# I2C_Breakout.net
KiCad netlist of a schematic drawn in Altium Designer
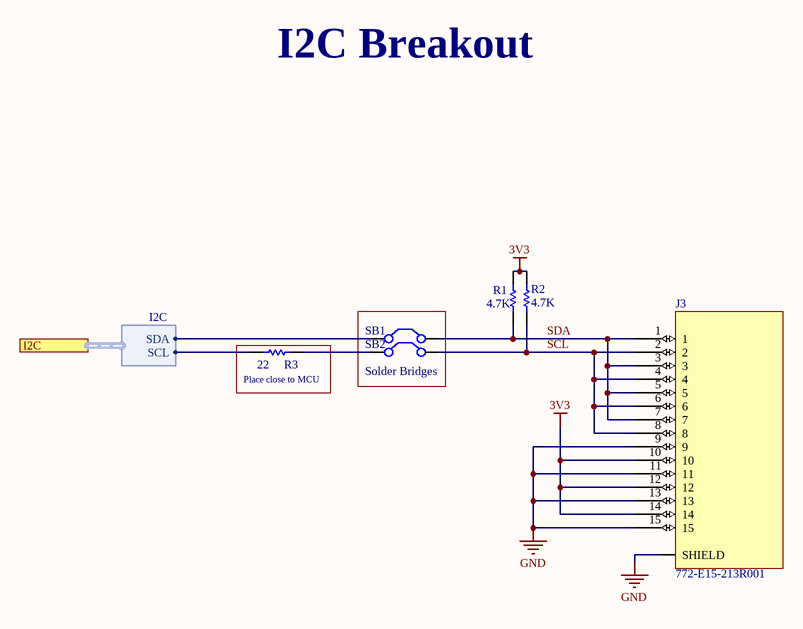
[diagram p0: I2C_Breakout.SchDoc]

(export (version "E")
  (design (tool "Eeschema 10.0.6"))
  (components
    (comp (ref "J3")
      (value "772-E15-213R001")
      (footprint "LaunchyRIOFootprints:15-Pos D-Sub")
      (description "15-Position Connector")
      (fields (field (name "DIGIKEY PART NUMBER") "NOR1010-ND"))
      (libsource (lib "LaunchyRIOComponents") (part "15-Position Connector"))
    )
    (comp (ref "R1")
      (value "4.7K")
      (footprint "0402")
      (description "Resistor")
      (fields (field (name "Comment") "Res1"))
      (libsource (lib "Miscellaneous Devices") (part "Res1"))
    )
    (comp (ref "R2")
      (value "4.7K")
      (footprint "0402")
      (description "Resistor")
      (fields (field (name "Comment") "Res1"))
      (libsource (lib "Miscellaneous Devices") (part "Res1"))
    )
    (comp (ref "R3")
      (value "22")
      (footprint "0402")
      (description "Resistor")
      (fields (field (name "Comment") "Res1"))
      (libsource (lib "Miscellaneous Devices") (part "Res1"))
    )
    (comp (ref "SB1")
      (value "Solder Bridge")
      (footprint "SB-2pos")
      (description "Jumper Wire")
      (libsource (lib "Miscellaneous Devices") (part "Jumper"))
    )
    (comp (ref "SB2")
      (value "Solder Bridge")
      (footprint "SB-2pos")
      (description "Jumper Wire")
      (libsource (lib "Miscellaneous Devices") (part "Jumper"))
    )
  )
  (nets
    (net (code "2") (name "/SCL") (class "Default")
      (node (ref "J3") (pin "2") (pinfunction "2_2") (pintype "bidirectional"))
      (node (ref "J3") (pin "4") (pinfunction "4_4") (pintype "bidirectional"))
      (node (ref "J3") (pin "6") (pinfunction "6_6") (pintype "bidirectional"))
      (node (ref "J3") (pin "8") (pinfunction "8_8") (pintype "bidirectional"))
      (node (ref "R2") (pin "1") (pinfunction "1_1") (pintype "passive"))
      (node (ref "SB2") (pin "2") (pinfunction "C2_2") (pintype "passive"))
    )
    (net (code "3") (name "/SDA") (class "Default")
      (node (ref "J3") (pin "1") (pinfunction "1_1") (pintype "bidirectional"))
      (node (ref "J3") (pin "3") (pinfunction "3_3") (pintype "bidirectional"))
      (node (ref "J3") (pin "5") (pinfunction "5_5") (pintype "bidirectional"))
      (node (ref "J3") (pin "7") (pinfunction "7_7") (pintype "bidirectional"))
      (node (ref "R1") (pin "1") (pinfunction "1_1") (pintype "passive"))
      (node (ref "SB1") (pin "2") (pinfunction "C2_2") (pintype "passive"))
    )
    (net (code "5") (name "3V3") (class "Default")
      (node (ref "J3") (pin "10") (pinfunction "10_10") (pintype "bidirectional"))
      (node (ref "J3") (pin "12") (pinfunction "12_12") (pintype "bidirectional"))
      (node (ref "J3") (pin "14") (pinfunction "14_14") (pintype "bidirectional"))
      (node (ref "R1") (pin "2") (pinfunction "2_2") (pintype "passive"))
      (node (ref "R2") (pin "2") (pinfunction "2_2") (pintype "passive"))
    )
    (net (code "6") (name "GND") (class "Default")
      (node (ref "J3") (pin "11") (pinfunction "11_11") (pintype "bidirectional"))
      (node (ref "J3") (pin "13") (pinfunction "13_13") (pintype "bidirectional"))
      (node (ref "J3") (pin "15") (pinfunction "15_15") (pintype "bidirectional"))
      (node (ref "J3") (pin "9") (pinfunction "9_9") (pintype "bidirectional"))
      (node (ref "J3") (pin "SHIELD") (pinfunction "SHIELD_SHIELD") (pintype "passive"))
    )
    (net (code "7") (name "Net-(SB2-C1)") (class "Default")
      (node (ref "R3") (pin "2") (pinfunction "2_2") (pintype "passive"))
      (node (ref "SB2") (pin "1") (pinfunction "C1_1") (pintype "passive"))
    )
    (net (code "8") (name "unconnected-(R3-Pad1)") (class "Default")
      (node (ref "R3") (pin "1") (pinfunction "1_1") (pintype "passive"))
    )
    (net (code "9") (name "unconnected-(SB1-C1-Pad1)") (class "Default")
      (node (ref "SB1") (pin "1") (pinfunction "C1_1") (pintype "passive"))
    )
  )
)
